# tssop28.net
KiCad netlist of a schematic drawn in EAGLE
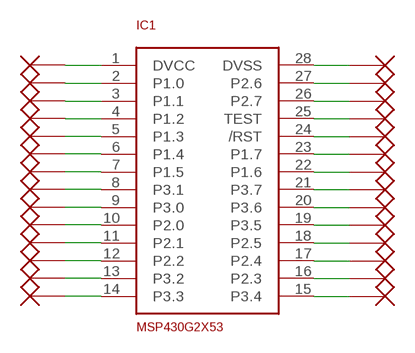
[diagram p0: schematic, sheet 1]

(export (version "E")
  (design (tool "Eeschema 10.0.6"))
  (components
    (comp (ref "IC1")
      (value "MSP430G2X53")
      (footprint "eagle-import:TSSOP28")
      (libsource (lib "eagle-import") (part "MSP430G2X53"))
    )
    (comp (ref "P1")
      (value "PIN")
      (footprint "eagle-import:PIN")
      (libsource (lib "eagle-import") (part "PIN"))
    )
    (comp (ref "P2")
      (value "PIN")
      (footprint "eagle-import:PIN")
      (libsource (lib "eagle-import") (part "PIN"))
    )
    (comp (ref "P3")
      (value "PIN")
      (footprint "eagle-import:PIN")
      (libsource (lib "eagle-import") (part "PIN"))
    )
    (comp (ref "P4")
      (value "PIN")
      (footprint "eagle-import:PIN")
      (libsource (lib "eagle-import") (part "PIN"))
    )
    (comp (ref "P5")
      (value "PIN")
      (footprint "eagle-import:PIN")
      (libsource (lib "eagle-import") (part "PIN"))
    )
    (comp (ref "P6")
      (value "PIN")
      (footprint "eagle-import:PIN")
      (libsource (lib "eagle-import") (part "PIN"))
    )
    (comp (ref "P7")
      (value "PIN")
      (footprint "eagle-import:PIN")
      (libsource (lib "eagle-import") (part "PIN"))
    )
    (comp (ref "P8")
      (value "PIN")
      (footprint "eagle-import:PIN")
      (libsource (lib "eagle-import") (part "PIN"))
    )
    (comp (ref "P9")
      (value "PIN")
      (footprint "eagle-import:PIN")
      (libsource (lib "eagle-import") (part "PIN"))
    )
    (comp (ref "P10")
      (value "PIN")
      (footprint "eagle-import:PIN")
      (libsource (lib "eagle-import") (part "PIN"))
    )
    (comp (ref "P11")
      (value "PIN")
      (footprint "eagle-import:PIN")
      (libsource (lib "eagle-import") (part "PIN"))
    )
    (comp (ref "P12")
      (value "PIN")
      (footprint "eagle-import:PIN")
      (libsource (lib "eagle-import") (part "PIN"))
    )
    (comp (ref "P13")
      (value "PIN")
      (footprint "eagle-import:PIN")
      (libsource (lib "eagle-import") (part "PIN"))
    )
    (comp (ref "P14")
      (value "PIN")
      (footprint "eagle-import:PIN")
      (libsource (lib "eagle-import") (part "PIN"))
    )
    (comp (ref "P15")
      (value "PIN")
      (footprint "eagle-import:PIN")
      (libsource (lib "eagle-import") (part "PIN"))
    )
    (comp (ref "P16")
      (value "PIN")
      (footprint "eagle-import:PIN")
      (libsource (lib "eagle-import") (part "PIN"))
    )
    (comp (ref "P17")
      (value "PIN")
      (footprint "eagle-import:PIN")
      (libsource (lib "eagle-import") (part "PIN"))
    )
    (comp (ref "P18")
      (value "PIN")
      (footprint "eagle-import:PIN")
      (libsource (lib "eagle-import") (part "PIN"))
    )
    (comp (ref "P19")
      (value "PIN")
      (footprint "eagle-import:PIN")
      (libsource (lib "eagle-import") (part "PIN"))
    )
    (comp (ref "P20")
      (value "PIN")
      (footprint "eagle-import:PIN")
      (libsource (lib "eagle-import") (part "PIN"))
    )
    (comp (ref "P21")
      (value "PIN")
      (footprint "eagle-import:PIN")
      (libsource (lib "eagle-import") (part "PIN"))
    )
    (comp (ref "P22")
      (value "PIN")
      (footprint "eagle-import:PIN")
      (libsource (lib "eagle-import") (part "PIN"))
    )
    (comp (ref "P23")
      (value "PIN")
      (footprint "eagle-import:PIN")
      (libsource (lib "eagle-import") (part "PIN"))
    )
    (comp (ref "P24")
      (value "PIN")
      (footprint "eagle-import:PIN")
      (libsource (lib "eagle-import") (part "PIN"))
    )
    (comp (ref "P25")
      (value "PIN")
      (footprint "eagle-import:PIN")
      (libsource (lib "eagle-import") (part "PIN"))
    )
    (comp (ref "P26")
      (value "PIN")
      (footprint "eagle-import:PIN")
      (libsource (lib "eagle-import") (part "PIN"))
    )
    (comp (ref "P27")
      (value "PIN")
      (footprint "eagle-import:PIN")
      (libsource (lib "eagle-import") (part "PIN"))
    )
    (comp (ref "P28")
      (value "PIN")
      (footprint "eagle-import:PIN")
      (libsource (lib "eagle-import") (part "PIN"))
    )
  )
  (nets
    (net (code "1") (name "Net-(IC1-DVCC)") (class "Default")
      (node (ref "IC1") (pin "1") (pinfunction "DVCC_1") (pintype "bidirectional"))
      (node (ref "P1") (pin "P$1") (pinfunction "P$1_P$1") (pintype "bidirectional"))
    )
    (net (code "2") (name "Net-(IC1-DVSS)") (class "Default")
      (node (ref "IC1") (pin "28") (pinfunction "DVSS_28") (pintype "bidirectional"))
      (node (ref "P15") (pin "P$1") (pinfunction "P$1_P$1") (pintype "bidirectional"))
    )
    (net (code "3") (name "Net-(IC1-P1.0)") (class "Default")
      (node (ref "IC1") (pin "2") (pinfunction "P1.0_2") (pintype "bidirectional"))
      (node (ref "P2") (pin "P$1") (pinfunction "P$1_P$1") (pintype "bidirectional"))
    )
    (net (code "4") (name "Net-(IC1-P1.1)") (class "Default")
      (node (ref "IC1") (pin "3") (pinfunction "P1.1_3") (pintype "bidirectional"))
      (node (ref "P3") (pin "P$1") (pinfunction "P$1_P$1") (pintype "bidirectional"))
    )
    (net (code "5") (name "Net-(IC1-P1.2)") (class "Default")
      (node (ref "IC1") (pin "4") (pinfunction "P1.2_4") (pintype "bidirectional"))
      (node (ref "P4") (pin "P$1") (pinfunction "P$1_P$1") (pintype "bidirectional"))
    )
    (net (code "6") (name "Net-(IC1-P1.3)") (class "Default")
      (node (ref "IC1") (pin "5") (pinfunction "P1.3_5") (pintype "bidirectional"))
      (node (ref "P5") (pin "P$1") (pinfunction "P$1_P$1") (pintype "bidirectional"))
    )
    (net (code "7") (name "Net-(IC1-P1.4)") (class "Default")
      (node (ref "IC1") (pin "6") (pinfunction "P1.4_6") (pintype "bidirectional"))
      (node (ref "P6") (pin "P$1") (pinfunction "P$1_P$1") (pintype "bidirectional"))
    )
    (net (code "8") (name "Net-(IC1-P1.5)") (class "Default")
      (node (ref "IC1") (pin "7") (pinfunction "P1.5_7") (pintype "bidirectional"))
      (node (ref "P7") (pin "P$1") (pinfunction "P$1_P$1") (pintype "bidirectional"))
    )
    (net (code "9") (name "Net-(IC1-P1.6)") (class "Default")
      (node (ref "IC1") (pin "22") (pinfunction "P1.6_22") (pintype "bidirectional"))
      (node (ref "P21") (pin "P$1") (pinfunction "P$1_P$1") (pintype "bidirectional"))
    )
    (net (code "10") (name "Net-(IC1-P1.7)") (class "Default")
      (node (ref "IC1") (pin "23") (pinfunction "P1.7_23") (pintype "bidirectional"))
      (node (ref "P20") (pin "P$1") (pinfunction "P$1_P$1") (pintype "bidirectional"))
    )
    (net (code "11") (name "Net-(IC1-P2.0)") (class "Default")
      (node (ref "IC1") (pin "10") (pinfunction "P2.0_10") (pintype "bidirectional"))
      (node (ref "P10") (pin "P$1") (pinfunction "P$1_P$1") (pintype "bidirectional"))
    )
    (net (code "12") (name "Net-(IC1-P2.1)") (class "Default")
      (node (ref "IC1") (pin "11") (pinfunction "P2.1_11") (pintype "bidirectional"))
      (node (ref "P11") (pin "P$1") (pinfunction "P$1_P$1") (pintype "bidirectional"))
    )
    (net (code "13") (name "Net-(IC1-P2.2)") (class "Default")
      (node (ref "IC1") (pin "12") (pinfunction "P2.2_12") (pintype "bidirectional"))
      (node (ref "P12") (pin "P$1") (pinfunction "P$1_P$1") (pintype "bidirectional"))
    )
    (net (code "14") (name "Net-(IC1-P2.3)") (class "Default")
      (node (ref "IC1") (pin "16") (pinfunction "P2.3_16") (pintype "bidirectional"))
      (node (ref "P27") (pin "P$1") (pinfunction "P$1_P$1") (pintype "bidirectional"))
    )
    (net (code "15") (name "Net-(IC1-P2.4)") (class "Default")
      (node (ref "IC1") (pin "17") (pinfunction "P2.4_17") (pintype "bidirectional"))
      (node (ref "P26") (pin "P$1") (pinfunction "P$1_P$1") (pintype "bidirectional"))
    )
    (net (code "16") (name "Net-(IC1-P2.5)") (class "Default")
      (node (ref "IC1") (pin "18") (pinfunction "P2.5_18") (pintype "bidirectional"))
      (node (ref "P25") (pin "P$1") (pinfunction "P$1_P$1") (pintype "bidirectional"))
    )
    (net (code "17") (name "Net-(IC1-P2.6)") (class "Default")
      (node (ref "IC1") (pin "27") (pinfunction "P2.6_27") (pintype "bidirectional"))
      (node (ref "P16") (pin "P$1") (pinfunction "P$1_P$1") (pintype "bidirectional"))
    )
    (net (code "18") (name "Net-(IC1-P2.7)") (class "Default")
      (node (ref "IC1") (pin "26") (pinfunction "P2.7_26") (pintype "bidirectional"))
      (node (ref "P17") (pin "P$1") (pinfunction "P$1_P$1") (pintype "bidirectional"))
    )
    (net (code "19") (name "Net-(IC1-P3.0)") (class "Default")
      (node (ref "IC1") (pin "9") (pinfunction "P3.0_9") (pintype "bidirectional"))
      (node (ref "P9") (pin "P$1") (pinfunction "P$1_P$1") (pintype "bidirectional"))
    )
    (net (code "20") (name "Net-(IC1-P3.1)") (class "Default")
      (node (ref "IC1") (pin "8") (pinfunction "P3.1_8") (pintype "bidirectional"))
      (node (ref "P8") (pin "P$1") (pinfunction "P$1_P$1") (pintype "bidirectional"))
    )
    (net (code "21") (name "Net-(IC1-P3.2)") (class "Default")
      (node (ref "IC1") (pin "13") (pinfunction "P3.2_13") (pintype "bidirectional"))
      (node (ref "P13") (pin "P$1") (pinfunction "P$1_P$1") (pintype "bidirectional"))
    )
    (net (code "22") (name "Net-(IC1-P3.3)") (class "Default")
      (node (ref "IC1") (pin "14") (pinfunction "P3.3_14") (pintype "bidirectional"))
      (node (ref "P14") (pin "P$1") (pinfunction "P$1_P$1") (pintype "bidirectional"))
    )
    (net (code "23") (name "Net-(IC1-P3.4)") (class "Default")
      (node (ref "IC1") (pin "15") (pinfunction "P3.4_15") (pintype "bidirectional"))
      (node (ref "P28") (pin "P$1") (pinfunction "P$1_P$1") (pintype "bidirectional"))
    )
    (net (code "24") (name "Net-(IC1-P3.5)") (class "Default")
      (node (ref "IC1") (pin "19") (pinfunction "P3.5_19") (pintype "bidirectional"))
      (node (ref "P24") (pin "P$1") (pinfunction "P$1_P$1") (pintype "bidirectional"))
    )
    (net (code "25") (name "Net-(IC1-P3.6)") (class "Default")
      (node (ref "IC1") (pin "20") (pinfunction "P3.6_20") (pintype "bidirectional"))
      (node (ref "P23") (pin "P$1") (pinfunction "P$1_P$1") (pintype "bidirectional"))
    )
    (net (code "26") (name "Net-(IC1-P3.7)") (class "Default")
      (node (ref "IC1") (pin "21") (pinfunction "P3.7_21") (pintype "bidirectional"))
      (node (ref "P22") (pin "P$1") (pinfunction "P$1_P$1") (pintype "bidirectional"))
    )
    (net (code "27") (name "Net-(IC1-TEST)") (class "Default")
      (node (ref "IC1") (pin "25") (pinfunction "TEST_25") (pintype "bidirectional"))
      (node (ref "P18") (pin "P$1") (pinfunction "P$1_P$1") (pintype "bidirectional"))
    )
    (net (code "28") (name "Net-(IC1-{slash}RST)") (class "Default")
      (node (ref "IC1") (pin "24") (pinfunction "/RST_24") (pintype "bidirectional"))
      (node (ref "P19") (pin "P$1") (pinfunction "P$1_P$1") (pintype "bidirectional"))
    )
  )
)
